# VL53L1X.net
KiCad netlist of a schematic drawn in Altium Designer
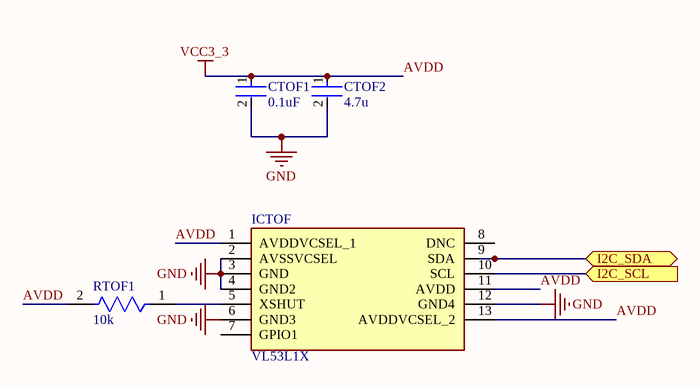
[diagram p0: VL53L1X.SchDoc]

(export (version "E")
  (design (tool "Eeschema 10.0.6"))
  (components
    (comp (ref "CTOF1")
      (value "0.1uF")
      (footprint "FP-CL10-IPC_C")
      (description "Cap Ceramic 100nF 50V X7R ±20% Pad SMD 0603 +125°C T/R")
      (fields (field (name "TOLERANCE") "20%"))
      (libsource (lib "Altium Content Vault") (part "b4654b650e69147ec39a6b967a45e02"))
    )
    (comp (ref "CTOF2")
      (value "4.7u")
      (footprint "FP-CL10-IPC_C")
      (description "Cap Ceramic 4.7uF 10V X5R ±10% Pad SMD 0603 +85°C T/R")
      (fields (field (name "TOLERANCE") "10%"))
      (libsource (lib "Altium Content Vault") (part "b4654b650e69147ec39a6b967a45e02"))
    )
    (comp (ref "ICTOF")
      (value "VL53L1X")
      (footprint "VL53L1X")
      (description "Integrated Circuit")
      (libsource (lib "James Whitehead") (part "VL53L1X"))
    )
    (comp (ref "RTOF1")
      (value "10k")
      (footprint "FP-ERJ3G-IPC_C")
      (description "RES SMD 10K OHM 5% 1/10W 0603")
      (fields (field (name "TOLERANCE") "5%"))
      (libsource (lib "Altium Content Vault") (part "1029c3af85768c4190bb7ad29bc67b5"))
    )
  )
  (nets
    (net (code "1") (name "/I2C_SCL") (class "Default")
      (node (ref "ICTOF") (pin "10") (pinfunction "SCL_10") (pintype "passive"))
    )
    (net (code "2") (name "/I2C_SDA") (class "Default")
      (node (ref "ICTOF") (pin "9") (pinfunction "SDA_9") (pintype "passive"))
    )
    (net (code "3") (name "GND") (class "Default")
      (node (ref "CTOF1") (pin "2") (pinfunction "2_2") (pintype "passive"))
      (node (ref "CTOF2") (pin "2") (pinfunction "2_2") (pintype "passive"))
      (node (ref "ICTOF") (pin "12") (pinfunction "GND4_12") (pintype "passive"))
      (node (ref "ICTOF") (pin "2") (pinfunction "AVSSVCSEL_2") (pintype "passive"))
      (node (ref "ICTOF") (pin "3") (pinfunction "GND_3") (pintype "passive"))
      (node (ref "ICTOF") (pin "4") (pinfunction "GND2_4") (pintype "passive"))
      (node (ref "ICTOF") (pin "6") (pinfunction "GND3_6") (pintype "passive"))
    )
    (net (code "4") (name "Net-(ICTOF-XSHUT)") (class "Default")
      (node (ref "ICTOF") (pin "5") (pinfunction "XSHUT_5") (pintype "passive"))
      (node (ref "RTOF1") (pin "1") (pinfunction "1_1") (pintype "passive"))
    )
    (net (code "5") (name "VCC3_3") (class "Default")
      (node (ref "CTOF1") (pin "1") (pinfunction "1_1") (pintype "passive"))
      (node (ref "CTOF2") (pin "1") (pinfunction "1_1") (pintype "passive"))
      (node (ref "ICTOF") (pin "1") (pinfunction "AVDDVCSEL_1_1") (pintype "passive"))
      (node (ref "ICTOF") (pin "11") (pinfunction "AVDD_11") (pintype "passive"))
      (node (ref "ICTOF") (pin "13") (pinfunction "AVDDVCSEL_2_13") (pintype "passive"))
      (node (ref "RTOF1") (pin "2") (pinfunction "2_2") (pintype "passive"))
    )
    (net (code "6") (name "unconnected-(ICTOF-DNC-Pad8)") (class "Default")
      (node (ref "ICTOF") (pin "8") (pinfunction "DNC_8") (pintype "passive"))
    )
    (net (code "7") (name "unconnected-(ICTOF-GPIO1-Pad7)") (class "Default")
      (node (ref "ICTOF") (pin "7") (pinfunction "GPIO1_7") (pintype "passive"))
    )
  )
)
